# top.net
KiCad netlist of a schematic drawn in Altium Designer
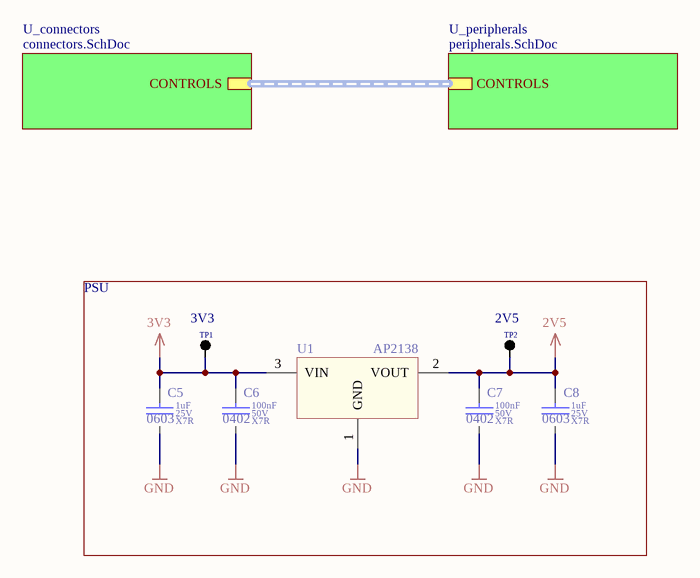
[diagram p0: top.SchDoc]

(export (version "E")
  (design (tool "Eeschema 10.0.6"))
  (components
    (comp (ref "C5")
      (value "1uF")
      (footprint "C_0603_1608")
      (description "Capacitor")
      (fields
        (field (name "DIELECTRIC") "X7R")
        (field (name "VOLTAGE") "25V")
        (field (name "SCH_FOOTPRINT") "0603")
        (field (name "PART NUMBER") "C_1uF_25V_X7R_0603_10")
        (field (name "MANUFACTURER") "Samsung")
      )
      (libsource (lib "Library") (part "C"))
    )
    (comp (ref "C6")
      (value "100nF")
      (footprint "C_0402_1005")
      (description "Capacitor")
      (fields
        (field (name "DIELECTRIC") "X7R")
        (field (name "VOLTAGE") "50V")
        (field (name "SCH_FOOTPRINT") "0402")
        (field (name "PART NUMBER") "C_100nF_50V_X7R_0402_10")
        (field (name "MANUFACTURER") "Murata")
      )
      (libsource (lib "Library") (part "C"))
    )
    (comp (ref "C7")
      (value "100nF")
      (footprint "C_0402_1005")
      (description "Capacitor")
      (fields
        (field (name "DIELECTRIC") "X7R")
        (field (name "VOLTAGE") "50V")
        (field (name "SCH_FOOTPRINT") "0402")
        (field (name "PART NUMBER") "C_100nF_50V_X7R_0402_10")
        (field (name "MANUFACTURER") "Murata")
      )
      (libsource (lib "Library") (part "C"))
    )
    (comp (ref "C8")
      (value "1uF")
      (footprint "C_0603_1608")
      (description "Capacitor")
      (fields
        (field (name "DIELECTRIC") "X7R")
        (field (name "VOLTAGE") "25V")
        (field (name "SCH_FOOTPRINT") "0603")
        (field (name "PART NUMBER") "C_1uF_25V_X7R_0603_10")
        (field (name "MANUFACTURER") "Samsung")
      )
      (libsource (lib "Library") (part "C"))
    )
    (comp (ref "TP1")
      (value "3V3")
      (footprint "TP_PAD")
      (description "Testpoint")
      (fields (field (name "PART NUMBER") "TP_PAD"))
      (libsource (lib "Library") (part "TP_TESTPOINT"))
    )
    (comp (ref "TP2")
      (value "2V5")
      (footprint "TP_PAD")
      (description "Testpoint")
      (fields (field (name "PART NUMBER") "TP_PAD"))
      (libsource (lib "Library") (part "TP_TESTPOINT"))
    )
    (comp (ref "U1")
      (value "AP2138")
      (footprint "AP2138")
      (description "IC: stabilizator napięcia; LDO,liniowy,nieregulowany; 2,5V; SMD")
      (libsource (lib "soldering_station") (part "AP2138"))
    )
  )
  (nets
    (net (code "2") (name "2V5") (class "Default")
      (node (ref "C7") (pin "1") (pinfunction "1_1") (pintype "passive"))
      (node (ref "C8") (pin "1") (pinfunction "1_1") (pintype "passive"))
      (node (ref "TP2") (pin "1") (pinfunction "TP_1") (pintype "passive"))
      (node (ref "U1") (pin "2") (pinfunction "VOUT_2") (pintype "passive"))
    )
    (net (code "3") (name "3V3") (class "Default")
      (node (ref "C5") (pin "1") (pinfunction "1_1") (pintype "passive"))
      (node (ref "C6") (pin "1") (pinfunction "1_1") (pintype "passive"))
      (node (ref "TP1") (pin "1") (pinfunction "TP_1") (pintype "passive"))
      (node (ref "U1") (pin "3") (pinfunction "VIN_3") (pintype "passive"))
    )
    (net (code "4") (name "GND") (class "Default")
      (node (ref "C5") (pin "2") (pinfunction "2_2") (pintype "passive"))
      (node (ref "C6") (pin "2") (pinfunction "2_2") (pintype "passive"))
      (node (ref "C7") (pin "2") (pinfunction "2_2") (pintype "passive"))
      (node (ref "C8") (pin "2") (pinfunction "2_2") (pintype "passive"))
      (node (ref "U1") (pin "1") (pinfunction "GND_1") (pintype "passive"))
    )
  )
)
